# rtc.net
KiCad netlist of a schematic drawn in Altium Designer
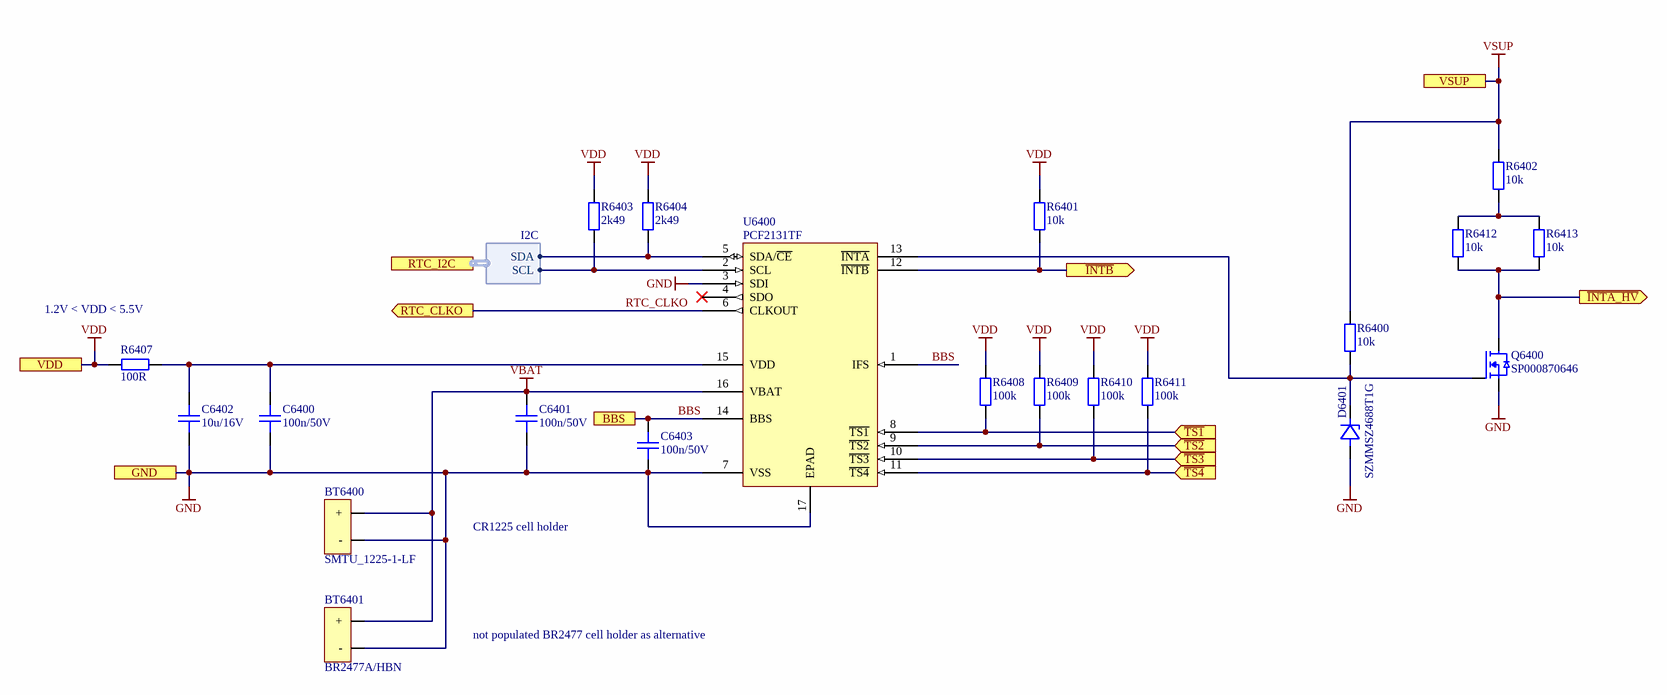
[diagram p0: rtc.SchDoc]

(export (version "E")
  (design (tool "Eeschema 10.0.6"))
  (components
    (comp (ref "BT6400")
      (value "SMTU_1225-1-LF")
      (footprint "SMTU_1225-1-LF")
      (description "SMTU 1225-1-LF, Battery Holder 1225")
      (fields (field (name "MANUFACTURER") "Renata"))
      (libsource (lib "OE750") (part "battery"))
    )
    (comp (ref "BT6401")
      (value "BR2477A/HBN")
      (footprint "BR2477A-HBN")
      (description "Coin Cell Battery 3V 1000mAH HI TEMP")
      (fields (field (name "MANUFACTURER") "Panasonic"))
      (libsource (lib "OE750") (part "battery"))
    )
    (comp (ref "C6400")
      (value "100n/50V")
      (footprint "CAPC1005X06N")
      (description "MLCC")
      (fields (field (name "PART NUMBER") "gen_C_ceramic_100n_50V_X7R_0402"))
      (libsource (lib "OE750") (part "C"))
    )
    (comp (ref "C6401")
      (value "100n/50V")
      (footprint "CAPC1005X06N")
      (description "MLCC")
      (fields (field (name "PART NUMBER") "gen_C_ceramic_100n_50V_X7R_0402"))
      (libsource (lib "OE750") (part "C"))
    )
    (comp (ref "C6402")
      (value "10u/16V")
      (footprint "CAPC2012X14N")
      (description "MLCC")
      (fields (field (name "PART NUMBER") "gen_C_ceramic_10u_16V_X7R_0805"))
      (libsource (lib "OE750") (part "C"))
    )
    (comp (ref "C6403")
      (value "100n/50V")
      (footprint "CAPC1005X06N")
      (description "MLCC")
      (fields (field (name "PART NUMBER") "gen_C_ceramic_100n_50V_X7R_0402"))
      (libsource (lib "OE750") (part "C"))
    )
    (comp (ref "D6401")
      (value "SZMMSZ4688T1G")
      (footprint "SOD-123_CASE-425-04-ISSUE-G")
      (description "Zener Diode")
      (fields (field (name "MANUFACTURER") "ON Semiconductor"))
      (libsource (lib "OE750") (part "D_Zener"))
    )
    (comp (ref "Q6400")
      (value "SP000870646")
      (footprint "SOT95P237X110-3N")
      (description "MOSFETs N-Ch 100V 190mA SOT-23-3")
      (fields (field (name "MANUFACTURER") "Infineon"))
      (libsource (lib "OE750") (part "NMOS"))
    )
    (comp (ref "R6400")
      (value "10k")
      (footprint "RESC1005X04N")
      (description "SMD Resistor 10k 0402")
      (fields (field (name "PART NUMBER") "gen_R_10k_0402") (field (name "TOLERANCE") "1%"))
      (libsource (lib "OE750") (part "R"))
    )
    (comp (ref "R6401")
      (value "10k")
      (footprint "RESC1005X04N")
      (description "SMD Resistor 10k 0402")
      (fields (field (name "PART NUMBER") "gen_R_10k_0402") (field (name "TOLERANCE") "1%"))
      (libsource (lib "OE750") (part "R"))
    )
    (comp (ref "R6402")
      (value "10k")
      (footprint "RESC1608X05N")
      (description "SMD Resistor 10k 0603")
      (fields (field (name "PART NUMBER") "gen_R_10k_0603") (field (name "TOLERANCE") "1%"))
      (libsource (lib "OE750") (part "R"))
    )
    (comp (ref "R6403")
      (value "2k49")
      (footprint "RESC1005X04N")
      (description "SMD Resistor 2k49 0402")
      (fields (field (name "PART NUMBER") "gen_R_2k49_0402") (field (name "TOLERANCE") "1%"))
      (libsource (lib "OE750") (part "R"))
    )
    (comp (ref "R6404")
      (value "2k49")
      (footprint "RESC1005X04N")
      (description "SMD Resistor 2k49 0402")
      (fields (field (name "PART NUMBER") "gen_R_2k49_0402") (field (name "TOLERANCE") "1%"))
      (libsource (lib "OE750") (part "R"))
    )
    (comp (ref "R6407")
      (value "100R")
      (footprint "RESC1005X04N")
      (description "SMD Resistor 100R 0402")
      (fields (field (name "PART NUMBER") "gen_R_100R_0402") (field (name "TOLERANCE") "1%"))
      (libsource (lib "OE750") (part "R"))
    )
    (comp (ref "R6408")
      (value "100k")
      (footprint "RESC1005X04N")
      (description "SMD Resistor 100k 0402")
      (fields (field (name "PART NUMBER") "gen_R_100k_0402") (field (name "TOLERANCE") "1%"))
      (libsource (lib "OE750") (part "R"))
    )
    (comp (ref "R6409")
      (value "100k")
      (footprint "RESC1005X04N")
      (description "SMD Resistor 100k 0402")
      (fields (field (name "PART NUMBER") "gen_R_100k_0402") (field (name "TOLERANCE") "1%"))
      (libsource (lib "OE750") (part "R"))
    )
    (comp (ref "R6410")
      (value "100k")
      (footprint "RESC1005X04N")
      (description "SMD Resistor 100k 0402")
      (fields (field (name "PART NUMBER") "gen_R_100k_0402") (field (name "TOLERANCE") "1%"))
      (libsource (lib "OE750") (part "R"))
    )
    (comp (ref "R6411")
      (value "100k")
      (footprint "RESC1005X04N")
      (description "SMD Resistor 100k 0402")
      (fields (field (name "PART NUMBER") "gen_R_100k_0402") (field (name "TOLERANCE") "1%"))
      (libsource (lib "OE750") (part "R"))
    )
    (comp (ref "R6412")
      (value "10k")
      (footprint "RESC1608X05N")
      (description "SMD Resistor 10k 0603")
      (fields (field (name "PART NUMBER") "gen_R_10k_0603") (field (name "TOLERANCE") "1%"))
      (libsource (lib "OE750") (part "R"))
    )
    (comp (ref "R6413")
      (value "10k")
      (footprint "RESC1608X05N")
      (description "SMD Resistor 10k 0603")
      (fields (field (name "PART NUMBER") "gen_R_10k_0603") (field (name "TOLERANCE") "1%"))
      (libsource (lib "OE750") (part "R"))
    )
    (comp (ref "U6400")
      (value "PCF2131TF")
      (footprint "NXP_SOT1992-1")
      (description "Ultra low power and high accurate RTC with integrated quartz crystal")
      (fields (field (name "MANUFACTURER") "NXP"))
      (libsource (lib "OE750") (part "PCF2131"))
    )
  )
  (nets
    (net (code "2") (name "/BBS") (class "Default")
      (node (ref "C6403") (pin "2") (pinfunction "2_2") (pintype "passive"))
      (node (ref "U6400") (pin "1") (pinfunction "IFS_1") (pintype "input"))
      (node (ref "U6400") (pin "14") (pinfunction "BBS_14") (pintype "power_in"))
    )
    (net (code "3") (name "/INTA_HV") (class "Default")
      (node (ref "Q6400") (pin "D") (pinfunction "D_D") (pintype "passive"))
      (node (ref "R6412") (pin "1") (pinfunction "1_1") (pintype "passive"))
      (node (ref "R6413") (pin "1") (pinfunction "1_1") (pintype "passive"))
    )
    (net (code "4") (name "/INTB") (class "Default")
      (node (ref "R6401") (pin "1") (pinfunction "1_1") (pintype "passive"))
      (node (ref "U6400") (pin "12") (pinfunction "INTB_12") (pintype "open_collector"))
    )
    (net (code "5") (name "/RTC_CLKO") (class "Default")
      (node (ref "U6400") (pin "6") (pinfunction "CLKOUT_6") (pintype "output"))
    )
    (net (code "6") (name "/TS1") (class "Default")
      (node (ref "R6408") (pin "1") (pinfunction "1_1") (pintype "passive"))
      (node (ref "U6400") (pin "8") (pinfunction "TS1_8") (pintype "input"))
    )
    (net (code "7") (name "/TS2") (class "Default")
      (node (ref "R6409") (pin "1") (pinfunction "1_1") (pintype "passive"))
      (node (ref "U6400") (pin "9") (pinfunction "TS2_9") (pintype "input"))
    )
    (net (code "8") (name "/TS3") (class "Default")
      (node (ref "R6410") (pin "1") (pinfunction "1_1") (pintype "passive"))
      (node (ref "U6400") (pin "10") (pinfunction "TS3_10") (pintype "input"))
    )
    (net (code "9") (name "/TS4") (class "Default")
      (node (ref "R6411") (pin "1") (pinfunction "1_1") (pintype "passive"))
      (node (ref "U6400") (pin "11") (pinfunction "TS4_11") (pintype "input"))
    )
    (net (code "11") (name "GND") (class "Default")
      (node (ref "BT6400") (pin "-") (pinfunction "-_-") (pintype "power_in"))
      (node (ref "BT6401") (pin "-") (pinfunction "-_-") (pintype "power_in"))
      (node (ref "C6400") (pin "1") (pinfunction "1_1") (pintype "passive"))
      (node (ref "C6401") (pin "1") (pinfunction "1_1") (pintype "passive"))
      (node (ref "C6402") (pin "1") (pinfunction "1_1") (pintype "passive"))
      (node (ref "C6403") (pin "1") (pinfunction "1_1") (pintype "passive"))
      (node (ref "D6401") (pin "2") (pinfunction "A_2") (pintype "passive"))
      (node (ref "Q6400") (pin "S") (pinfunction "S_S") (pintype "passive"))
      (node (ref "U6400") (pin "17") (pinfunction "EPAD_17") (pintype "power_in"))
      (node (ref "U6400") (pin "3") (pinfunction "SDI_3") (pintype "input"))
      (node (ref "U6400") (pin "7") (pinfunction "VSS_7") (pintype "power_in"))
    )
    (net (code "12") (name "Net-(D6401-K)") (class "Default")
      (node (ref "D6401") (pin "1") (pinfunction "K_1") (pintype "passive"))
      (node (ref "Q6400") (pin "G") (pinfunction "G_G") (pintype "passive"))
      (node (ref "R6400") (pin "1") (pinfunction "1_1") (pintype "passive"))
      (node (ref "U6400") (pin "13") (pinfunction "INTA_13") (pintype "open_collector"))
    )
    (net (code "13") (name "Net-(R6402-Pad1)") (class "Default")
      (node (ref "R6402") (pin "1") (pinfunction "1_1") (pintype "passive"))
      (node (ref "R6412") (pin "2") (pinfunction "2_2") (pintype "passive"))
      (node (ref "R6413") (pin "2") (pinfunction "2_2") (pintype "passive"))
    )
    (net (code "14") (name "Net-(U6400-SCL)") (class "Default")
      (node (ref "R6403") (pin "1") (pinfunction "1_1") (pintype "passive"))
      (node (ref "U6400") (pin "2") (pinfunction "SCL_2") (pintype "input"))
    )
    (net (code "15") (name "Net-(U6400-SDA{slash}~{CE})") (class "Default")
      (node (ref "R6404") (pin "1") (pinfunction "1_1") (pintype "passive"))
      (node (ref "U6400") (pin "5") (pinfunction "SDA/~{CE}_5") (pintype "bidirectional"))
    )
    (net (code "16") (name "Net-(U6400-VDD)") (class "Default")
      (node (ref "C6400") (pin "2") (pinfunction "2_2") (pintype "passive"))
      (node (ref "C6402") (pin "2") (pinfunction "2_2") (pintype "passive"))
      (node (ref "R6407") (pin "1") (pinfunction "1_1") (pintype "passive"))
      (node (ref "U6400") (pin "15") (pinfunction "VDD_15") (pintype "power_in"))
    )
    (net (code "17") (name "VBAT") (class "Default")
      (node (ref "BT6400") (pin "+") (pinfunction "+_+") (pintype "power_in"))
      (node (ref "BT6401") (pin "+") (pinfunction "+_+") (pintype "power_in"))
      (node (ref "C6401") (pin "2") (pinfunction "2_2") (pintype "passive"))
      (node (ref "U6400") (pin "16") (pinfunction "VBAT_16") (pintype "power_in"))
    )
    (net (code "18") (name "VDD") (class "Default")
      (node (ref "R6401") (pin "2") (pinfunction "2_2") (pintype "passive"))
      (node (ref "R6403") (pin "2") (pinfunction "2_2") (pintype "passive"))
      (node (ref "R6404") (pin "2") (pinfunction "2_2") (pintype "passive"))
      (node (ref "R6407") (pin "2") (pinfunction "2_2") (pintype "passive"))
      (node (ref "R6408") (pin "2") (pinfunction "2_2") (pintype "passive"))
      (node (ref "R6409") (pin "2") (pinfunction "2_2") (pintype "passive"))
      (node (ref "R6410") (pin "2") (pinfunction "2_2") (pintype "passive"))
      (node (ref "R6411") (pin "2") (pinfunction "2_2") (pintype "passive"))
    )
    (net (code "19") (name "VSUP") (class "Default")
      (node (ref "R6400") (pin "2") (pinfunction "2_2") (pintype "passive"))
      (node (ref "R6402") (pin "2") (pinfunction "2_2") (pintype "passive"))
    )
    (net (code "20") (name "unconnected-(U6400-SDO-Pad4)") (class "Default")
      (node (ref "U6400") (pin "4") (pinfunction "SDO_4") (pintype "output+no_connect"))
    )
  )
)
